# remote.net
KiCad netlist of a schematic drawn in Altium Designer
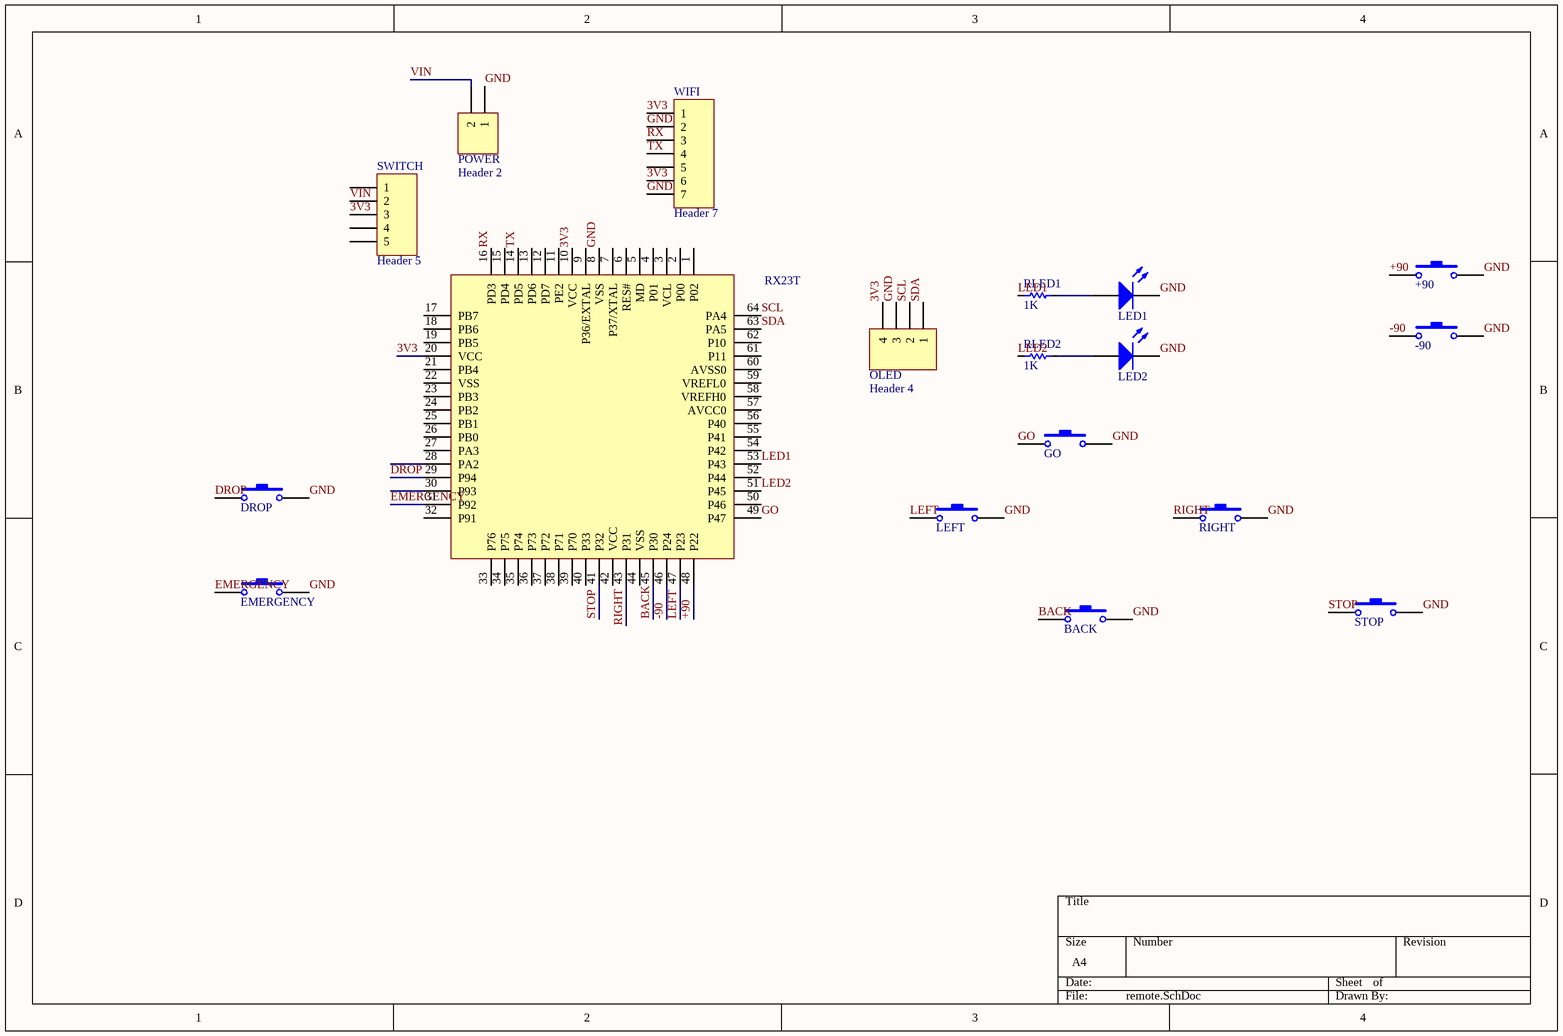
[diagram p0: remote.SchDoc]

(export (version "E")
  (design (tool "Eeschema 10.0.6"))
  (components
    (comp (ref "+90") (value "贴片轻触开关") (footprint "SW-6*6") (libsource (lib "RX23T") (part "贴片轻触开关")))
    (comp (ref "-90") (value "贴片轻触开关") (footprint "SW-6*6") (libsource (lib "RX23T") (part "贴片轻触开关")))
    (comp (ref "BACK") (value "贴片轻触开关") (footprint "SW-6*6") (libsource (lib "RX23T") (part "贴片轻触开关")))
    (comp (ref "DROP") (value "贴片轻触开关") (footprint "SW-6*6") (libsource (lib "RX23T") (part "贴片轻触开关")))
    (comp (ref "EMERGENCY") (value "贴片轻触开关") (footprint "SW-6*6") (libsource (lib "RX23T") (part "贴片轻触开关")))
    (comp (ref "GO") (value "贴片轻触开关") (footprint "SW-6*6") (libsource (lib "RX23T") (part "贴片轻触开关")))
    (comp (ref "LED1") (value "LED") (footprint "LED 3MM-R") (libsource (lib "RX23T") (part "LED")))
    (comp (ref "LED2") (value "LED") (footprint "LED 3MM-R") (libsource (lib "RX23T") (part "LED")))
    (comp (ref "LEFT") (value "贴片轻触开关") (footprint "SW-6*6") (libsource (lib "RX23T") (part "贴片轻触开关")))
    (comp (ref "OLED")
      (value "Header 4")
      (footprint "HDR1X4")
      (description "Header, 4-Pin")
      (fields (field (name "PUBLISHER") "Altium Limited"))
      (libsource (lib "Miscellaneous Connectors") (part "Header 4"))
    )
    (comp (ref "POWER")
      (value "Header 2")
      (footprint "HDR1X2")
      (description "Header, 2-Pin")
      (fields (field (name "PUBLISHER") "Altium Limited"))
      (libsource (lib "Miscellaneous Connectors") (part "Header 2"))
    )
    (comp (ref "RIGHT") (value "贴片轻触开关") (footprint "SW-6*6") (libsource (lib "RX23T") (part "贴片轻触开关")))
    (comp (ref "RLED1")
      (value "1K")
      (footprint "RS 1/4W")
      (description "R_0603")
      (libsource (lib "RX23T") (part "R"))
    )
    (comp (ref "RLED2")
      (value "1K")
      (footprint "RS 1/4W")
      (description "R_0603")
      (libsource (lib "RX23T") (part "R"))
    )
    (comp (ref "RX23T")
      (value "RX23T")
      (footprint "RFR")
      (libsource (lib "RECN_RX23T_OBE_V101") (part "RX23T"))
    )
    (comp (ref "STOP") (value "贴片轻触开关") (footprint "SW-6*6") (libsource (lib "RX23T") (part "贴片轻触开关")))
    (comp (ref "SWITCH")
      (value "Header 5")
      (footprint "HDR1X5")
      (description "Header, 5-Pin")
      (fields (field (name "PUBLISHER") "Altium Limited"))
      (libsource (lib "Miscellaneous Connectors") (part "Header 5"))
    )
    (comp (ref "WIFI")
      (value "Header 7")
      (footprint "HDR1X7")
      (description "Header, 7-Pin")
      (fields (field (name "PUBLISHER") "Altium Limited"))
      (libsource (lib "Miscellaneous Connectors") (part "Header 7"))
    )
  )
  (nets
    (net (code "1") (name "/+90") (class "Default")
      (node (ref "+90") (pin "1") (pinfunction "1_1") (pintype "passive"))
      (node (ref "RX23T") (pin "48") (pinfunction "P22_48") (pintype "passive"))
    )
    (net (code "2") (name "/-90") (class "Default")
      (node (ref "-90") (pin "1") (pinfunction "1_1") (pintype "passive"))
      (node (ref "RX23T") (pin "46") (pinfunction "P24_46") (pintype "passive"))
    )
    (net (code "3") (name "/3V3") (class "Default")
      (node (ref "OLED") (pin "4") (pinfunction "4_4") (pintype "passive"))
      (node (ref "RX23T") (pin "10") (pinfunction "VCC_10") (pintype "passive"))
      (node (ref "RX23T") (pin "20") (pinfunction "VCC_20") (pintype "passive"))
      (node (ref "SWITCH") (pin "3") (pinfunction "3_3") (pintype "passive"))
      (node (ref "WIFI") (pin "1") (pinfunction "1_1") (pintype "passive"))
      (node (ref "WIFI") (pin "6") (pinfunction "6_6") (pintype "passive"))
    )
    (net (code "4") (name "/BACK") (class "Default")
      (node (ref "BACK") (pin "1") (pinfunction "1_1") (pintype "passive"))
      (node (ref "RX23T") (pin "45") (pinfunction "P30_45") (pintype "passive"))
    )
    (net (code "5") (name "/DROP") (class "Default")
      (node (ref "DROP") (pin "1") (pinfunction "1_1") (pintype "passive"))
      (node (ref "RX23T") (pin "29") (pinfunction "P94_29") (pintype "passive"))
    )
    (net (code "6") (name "/EMERGENCY") (class "Default")
      (node (ref "EMERGENCY") (pin "1") (pinfunction "1_1") (pintype "passive"))
      (node (ref "RX23T") (pin "31") (pinfunction "P92_31") (pintype "passive"))
    )
    (net (code "7") (name "/GND") (class "Default")
      (node (ref "+90") (pin "2") (pinfunction "2_2") (pintype "passive"))
      (node (ref "-90") (pin "2") (pinfunction "2_2") (pintype "passive"))
      (node (ref "BACK") (pin "2") (pinfunction "2_2") (pintype "passive"))
      (node (ref "DROP") (pin "2") (pinfunction "2_2") (pintype "passive"))
      (node (ref "EMERGENCY") (pin "2") (pinfunction "2_2") (pintype "passive"))
      (node (ref "GO") (pin "2") (pinfunction "2_2") (pintype "passive"))
      (node (ref "LED1") (pin "2") (pinfunction "2_2") (pintype "passive"))
      (node (ref "LED2") (pin "2") (pinfunction "2_2") (pintype "passive"))
      (node (ref "LEFT") (pin "2") (pinfunction "2_2") (pintype "passive"))
      (node (ref "OLED") (pin "3") (pinfunction "3_3") (pintype "passive"))
      (node (ref "POWER") (pin "1") (pinfunction "1_1") (pintype "passive"))
      (node (ref "RIGHT") (pin "2") (pinfunction "2_2") (pintype "passive"))
      (node (ref "RX23T") (pin "8") (pinfunction "VSS_8") (pintype "passive"))
      (node (ref "STOP") (pin "2") (pinfunction "2_2") (pintype "passive"))
      (node (ref "WIFI") (pin "2") (pinfunction "2_2") (pintype "passive"))
      (node (ref "WIFI") (pin "7") (pinfunction "7_7") (pintype "passive"))
    )
    (net (code "8") (name "/GO") (class "Default")
      (node (ref "GO") (pin "1") (pinfunction "1_1") (pintype "passive"))
      (node (ref "RX23T") (pin "49") (pinfunction "P47_49") (pintype "passive"))
    )
    (net (code "9") (name "/LED1") (class "Default")
      (node (ref "RLED1") (pin "1") (pinfunction "1_1") (pintype "passive"))
      (node (ref "RX23T") (pin "53") (pinfunction "P43_53") (pintype "passive"))
    )
    (net (code "10") (name "/LED2") (class "Default")
      (node (ref "RLED2") (pin "1") (pinfunction "1_1") (pintype "passive"))
      (node (ref "RX23T") (pin "51") (pinfunction "P45_51") (pintype "passive"))
    )
    (net (code "11") (name "/LEFT") (class "Default")
      (node (ref "LEFT") (pin "1") (pinfunction "1_1") (pintype "passive"))
      (node (ref "RX23T") (pin "47") (pinfunction "P23_47") (pintype "passive"))
    )
    (net (code "12") (name "/RIGHT") (class "Default")
      (node (ref "RIGHT") (pin "1") (pinfunction "1_1") (pintype "passive"))
      (node (ref "RX23T") (pin "43") (pinfunction "P31_43") (pintype "passive"))
    )
    (net (code "13") (name "/RX") (class "Default")
      (node (ref "RX23T") (pin "16") (pinfunction "PD3_16") (pintype "passive"))
      (node (ref "WIFI") (pin "3") (pinfunction "3_3") (pintype "passive"))
    )
    (net (code "14") (name "/SCL") (class "Default")
      (node (ref "OLED") (pin "2") (pinfunction "2_2") (pintype "passive"))
      (node (ref "RX23T") (pin "64") (pinfunction "PA4_64") (pintype "passive"))
    )
    (net (code "15") (name "/SDA") (class "Default")
      (node (ref "OLED") (pin "1") (pinfunction "1_1") (pintype "passive"))
      (node (ref "RX23T") (pin "63") (pinfunction "PA5_63") (pintype "passive"))
    )
    (net (code "16") (name "/STOP") (class "Default")
      (node (ref "RX23T") (pin "41") (pinfunction "P32_41") (pintype "passive"))
      (node (ref "STOP") (pin "1") (pinfunction "1_1") (pintype "passive"))
    )
    (net (code "17") (name "/TX") (class "Default")
      (node (ref "RX23T") (pin "14") (pinfunction "PD5_14") (pintype "passive"))
      (node (ref "WIFI") (pin "4") (pinfunction "4_4") (pintype "passive"))
    )
    (net (code "18") (name "/VIN") (class "Default")
      (node (ref "POWER") (pin "2") (pinfunction "2_2") (pintype "passive"))
      (node (ref "SWITCH") (pin "2") (pinfunction "2_2") (pintype "passive"))
    )
    (net (code "19") (name "Net-(LED1-Pad1)") (class "Default")
      (node (ref "LED1") (pin "1") (pinfunction "1_1") (pintype "passive"))
      (node (ref "RLED1") (pin "2") (pinfunction "2_2") (pintype "passive"))
    )
    (net (code "20") (name "Net-(LED2-Pad1)") (class "Default")
      (node (ref "LED2") (pin "1") (pinfunction "1_1") (pintype "passive"))
      (node (ref "RLED2") (pin "2") (pinfunction "2_2") (pintype "passive"))
    )
    (net (code "21") (name "unconnected-(RX23T-AVCC0-Pad57)") (class "Default")
      (node (ref "RX23T") (pin "57") (pinfunction "AVCC0_57") (pintype "passive"))
    )
    (net (code "22") (name "unconnected-(RX23T-AVSS0-Pad60)") (class "Default")
      (node (ref "RX23T") (pin "60") (pinfunction "AVSS0_60") (pintype "passive"))
    )
    (net (code "23") (name "unconnected-(RX23T-MD-Pad5)") (class "Default")
      (node (ref "RX23T") (pin "5") (pinfunction "MD_5") (pintype "passive"))
    )
    (net (code "24") (name "unconnected-(RX23T-P00-Pad2)") (class "Default")
      (node (ref "RX23T") (pin "2") (pinfunction "P00_2") (pintype "passive"))
    )
    (net (code "25") (name "unconnected-(RX23T-P01-Pad4)") (class "Default")
      (node (ref "RX23T") (pin "4") (pinfunction "P01_4") (pintype "passive"))
    )
    (net (code "26") (name "unconnected-(RX23T-P02-Pad1)") (class "Default")
      (node (ref "RX23T") (pin "1") (pinfunction "P02_1") (pintype "passive"))
    )
    (net (code "27") (name "unconnected-(RX23T-P10-Pad62)") (class "Default")
      (node (ref "RX23T") (pin "62") (pinfunction "P10_62") (pintype "passive"))
    )
    (net (code "28") (name "unconnected-(RX23T-P11-Pad61)") (class "Default")
      (node (ref "RX23T") (pin "61") (pinfunction "P11_61") (pintype "passive"))
    )
    (net (code "29") (name "unconnected-(RX23T-P33-Pad40)") (class "Default")
      (node (ref "RX23T") (pin "40") (pinfunction "P33_40") (pintype "passive"))
    )
    (net (code "30") (name "unconnected-(RX23T-P36{slash}EXTAL-Pad9)") (class "Default")
      (node (ref "RX23T") (pin "9") (pinfunction "P36/EXTAL_9") (pintype "passive"))
    )
    (net (code "31") (name "unconnected-(RX23T-P37{slash}XTAL-Pad7)") (class "Default")
      (node (ref "RX23T") (pin "7") (pinfunction "P37/XTAL_7") (pintype "passive"))
    )
    (net (code "32") (name "unconnected-(RX23T-P40-Pad56)") (class "Default")
      (node (ref "RX23T") (pin "56") (pinfunction "P40_56") (pintype "passive"))
    )
    (net (code "33") (name "unconnected-(RX23T-P41-Pad55)") (class "Default")
      (node (ref "RX23T") (pin "55") (pinfunction "P41_55") (pintype "passive"))
    )
    (net (code "34") (name "unconnected-(RX23T-P42-Pad54)") (class "Default")
      (node (ref "RX23T") (pin "54") (pinfunction "P42_54") (pintype "passive"))
    )
    (net (code "35") (name "unconnected-(RX23T-P44-Pad52)") (class "Default")
      (node (ref "RX23T") (pin "52") (pinfunction "P44_52") (pintype "passive"))
    )
    (net (code "36") (name "unconnected-(RX23T-P46-Pad50)") (class "Default")
      (node (ref "RX23T") (pin "50") (pinfunction "P46_50") (pintype "passive"))
    )
    (net (code "37") (name "unconnected-(RX23T-P70-Pad39)") (class "Default")
      (node (ref "RX23T") (pin "39") (pinfunction "P70_39") (pintype "passive"))
    )
    (net (code "38") (name "unconnected-(RX23T-P71-Pad38)") (class "Default")
      (node (ref "RX23T") (pin "38") (pinfunction "P71_38") (pintype "passive"))
    )
    (net (code "39") (name "unconnected-(RX23T-P72-Pad37)") (class "Default")
      (node (ref "RX23T") (pin "37") (pinfunction "P72_37") (pintype "passive"))
    )
    (net (code "40") (name "unconnected-(RX23T-P73-Pad36)") (class "Default")
      (node (ref "RX23T") (pin "36") (pinfunction "P73_36") (pintype "passive"))
    )
    (net (code "41") (name "unconnected-(RX23T-P74-Pad35)") (class "Default")
      (node (ref "RX23T") (pin "35") (pinfunction "P74_35") (pintype "passive"))
    )
    (net (code "42") (name "unconnected-(RX23T-P75-Pad34)") (class "Default")
      (node (ref "RX23T") (pin "34") (pinfunction "P75_34") (pintype "passive"))
    )
    (net (code "43") (name "unconnected-(RX23T-P76-Pad33)") (class "Default")
      (node (ref "RX23T") (pin "33") (pinfunction "P76_33") (pintype "passive"))
    )
    (net (code "44") (name "unconnected-(RX23T-P91-Pad32)") (class "Default")
      (node (ref "RX23T") (pin "32") (pinfunction "P91_32") (pintype "passive"))
    )
    (net (code "45") (name "unconnected-(RX23T-P93-Pad30)") (class "Default")
      (node (ref "RX23T") (pin "30") (pinfunction "P93_30") (pintype "passive"))
    )
    (net (code "46") (name "unconnected-(RX23T-PA2-Pad28)") (class "Default")
      (node (ref "RX23T") (pin "28") (pinfunction "PA2_28") (pintype "passive"))
    )
    (net (code "47") (name "unconnected-(RX23T-PA3-Pad27)") (class "Default")
      (node (ref "RX23T") (pin "27") (pinfunction "PA3_27") (pintype "passive"))
    )
    (net (code "48") (name "unconnected-(RX23T-PB0-Pad26)") (class "Default")
      (node (ref "RX23T") (pin "26") (pinfunction "PB0_26") (pintype "passive"))
    )
    (net (code "49") (name "unconnected-(RX23T-PB1-Pad25)") (class "Default")
      (node (ref "RX23T") (pin "25") (pinfunction "PB1_25") (pintype "passive"))
    )
    (net (code "50") (name "unconnected-(RX23T-PB2-Pad24)") (class "Default")
      (node (ref "RX23T") (pin "24") (pinfunction "PB2_24") (pintype "passive"))
    )
    (net (code "51") (name "unconnected-(RX23T-PB3-Pad23)") (class "Default")
      (node (ref "RX23T") (pin "23") (pinfunction "PB3_23") (pintype "passive"))
    )
    (net (code "52") (name "unconnected-(RX23T-PB4-Pad21)") (class "Default")
      (node (ref "RX23T") (pin "21") (pinfunction "PB4_21") (pintype "passive"))
    )
    (net (code "53") (name "unconnected-(RX23T-PB5-Pad19)") (class "Default")
      (node (ref "RX23T") (pin "19") (pinfunction "PB5_19") (pintype "passive"))
    )
    (net (code "54") (name "unconnected-(RX23T-PB6-Pad18)") (class "Default")
      (node (ref "RX23T") (pin "18") (pinfunction "PB6_18") (pintype "passive"))
    )
    (net (code "55") (name "unconnected-(RX23T-PB7-Pad17)") (class "Default")
      (node (ref "RX23T") (pin "17") (pinfunction "PB7_17") (pintype "passive"))
    )
    (net (code "56") (name "unconnected-(RX23T-PD4-Pad15)") (class "Default")
      (node (ref "RX23T") (pin "15") (pinfunction "PD4_15") (pintype "passive"))
    )
    (net (code "57") (name "unconnected-(RX23T-PD6-Pad13)") (class "Default")
      (node (ref "RX23T") (pin "13") (pinfunction "PD6_13") (pintype "passive"))
    )
    (net (code "58") (name "unconnected-(RX23T-PD7-Pad12)") (class "Default")
      (node (ref "RX23T") (pin "12") (pinfunction "PD7_12") (pintype "passive"))
    )
    (net (code "59") (name "unconnected-(RX23T-PE2-Pad11)") (class "Default")
      (node (ref "RX23T") (pin "11") (pinfunction "PE2_11") (pintype "passive"))
    )
    (net (code "60") (name "unconnected-(RX23T-RES#-Pad6)") (class "Default")
      (node (ref "RX23T") (pin "6") (pinfunction "RES#_6") (pintype "passive"))
    )
    (net (code "61") (name "unconnected-(RX23T-VCC-Pad42)") (class "Default")
      (node (ref "RX23T") (pin "42") (pinfunction "VCC_42") (pintype "passive"))
    )
    (net (code "62") (name "unconnected-(RX23T-VCL-Pad3)") (class "Default")
      (node (ref "RX23T") (pin "3") (pinfunction "VCL_3") (pintype "passive"))
    )
    (net (code "63") (name "unconnected-(RX23T-VREFH0-Pad58)") (class "Default")
      (node (ref "RX23T") (pin "58") (pinfunction "VREFH0_58") (pintype "passive"))
    )
    (net (code "64") (name "unconnected-(RX23T-VREFL0-Pad59)") (class "Default")
      (node (ref "RX23T") (pin "59") (pinfunction "VREFL0_59") (pintype "passive"))
    )
    (net (code "65") (name "unconnected-(RX23T-VSS-Pad22)") (class "Default")
      (node (ref "RX23T") (pin "22") (pinfunction "VSS_22") (pintype "passive"))
    )
    (net (code "66") (name "unconnected-(RX23T-VSS-Pad44)") (class "Default")
      (node (ref "RX23T") (pin "44") (pinfunction "VSS_44") (pintype "passive"))
    )
    (net (code "67") (name "unconnected-(SWITCH-Pad1)") (class "Default")
      (node (ref "SWITCH") (pin "1") (pinfunction "1_1") (pintype "passive"))
    )
    (net (code "68") (name "unconnected-(SWITCH-Pad4)") (class "Default")
      (node (ref "SWITCH") (pin "4") (pinfunction "4_4") (pintype "passive"))
    )
    (net (code "69") (name "unconnected-(SWITCH-Pad5)") (class "Default")
      (node (ref "SWITCH") (pin "5") (pinfunction "5_5") (pintype "passive"))
    )
    (net (code "70") (name "unconnected-(WIFI-Pad5)") (class "Default")
      (node (ref "WIFI") (pin "5") (pinfunction "5_5") (pintype "passive"))
    )
  )
)
